# design.net
KiCad netlist of a schematic drawn in Altium Designer
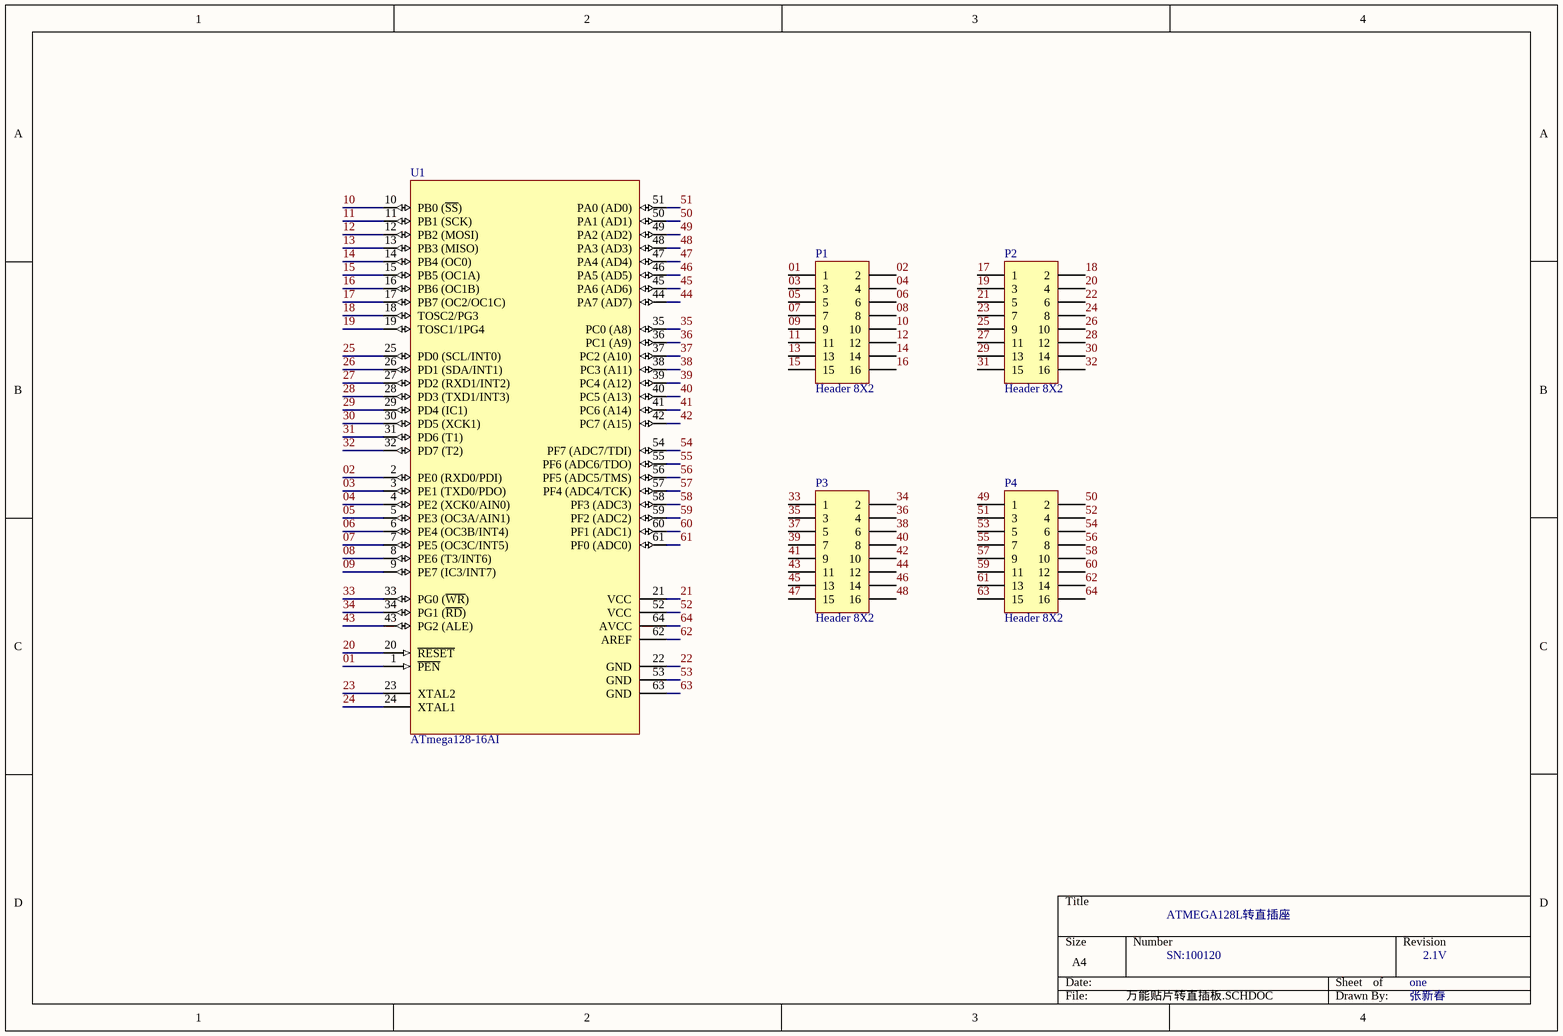
[diagram p0: 万能贴片转直插板.SCHDOC]

(export (version "E")
  (design (tool "Eeschema 10.0.6"))
  (components
    (comp (ref "P1")
      (value "Header 8X2")
      (footprint "HDR2X8")
      (description "Header, 8-Pin, Dual row")
      (fields (field (name "PUBLISHER") "Altium Limited"))
      (libsource (lib "Miscellaneous Connectors") (part "Header 8X2"))
    )
    (comp (ref "P2")
      (value "Header 8X2")
      (footprint "HDR2X8")
      (description "Header, 8-Pin, Dual row")
      (fields (field (name "PUBLISHER") "Altium Limited"))
      (libsource (lib "Miscellaneous Connectors") (part "Header 8X2"))
    )
    (comp (ref "P3")
      (value "Header 8X2")
      (footprint "HDR2X8")
      (description "Header, 8-Pin, Dual row")
      (fields (field (name "PUBLISHER") "Altium Limited"))
      (libsource (lib "Miscellaneous Connectors") (part "Header 8X2"))
    )
    (comp (ref "P4")
      (value "Header 8X2")
      (footprint "HDR2X8")
      (description "Header, 8-Pin, Dual row")
      (fields (field (name "PUBLISHER") "Altium Limited"))
      (libsource (lib "Miscellaneous Connectors") (part "Header 8X2"))
    )
    (comp (ref "U1")
      (value "ATmega128-16AI")
      (footprint "wanneng_2")
      (description "8-Bit AVR Microcontroller with 128K Bytes of In-System Programmable Flash Memory")
      (fields (field (name "PUBLISHER") "Altium Limited"))
      (libsource (lib "Atmel Microcontroller 8-Bit AVR") (part "ATmega128-16AI"))
    )
  )
  (nets
    (net (code "1") (name "/01") (class "Default")
      (node (ref "P1") (pin "1") (pinfunction "1_1") (pintype "passive"))
      (node (ref "U1") (pin "1") (pinfunction "~{PEN}_1") (pintype "input"))
    )
    (net (code "2") (name "/02") (class "Default")
      (node (ref "P1") (pin "2") (pinfunction "2_2") (pintype "passive"))
      (node (ref "U1") (pin "2") (pinfunction "PE0_(RXD0/PDI)_2") (pintype "bidirectional"))
    )
    (net (code "3") (name "/03") (class "Default")
      (node (ref "P1") (pin "3") (pinfunction "3_3") (pintype "passive"))
      (node (ref "U1") (pin "3") (pinfunction "PE1_(TXD0/PDO)_3") (pintype "bidirectional"))
    )
    (net (code "4") (name "/04") (class "Default")
      (node (ref "P1") (pin "4") (pinfunction "4_4") (pintype "passive"))
      (node (ref "U1") (pin "4") (pinfunction "PE2_(XCK0/AIN0)_4") (pintype "bidirectional"))
    )
    (net (code "5") (name "/05") (class "Default")
      (node (ref "P1") (pin "5") (pinfunction "5_5") (pintype "passive"))
      (node (ref "U1") (pin "5") (pinfunction "PE3_(OC3A/AIN1)_5") (pintype "bidirectional"))
    )
    (net (code "6") (name "/06") (class "Default")
      (node (ref "P1") (pin "6") (pinfunction "6_6") (pintype "passive"))
      (node (ref "U1") (pin "6") (pinfunction "PE4_(OC3B/INT4)_6") (pintype "bidirectional"))
    )
    (net (code "7") (name "/07") (class "Default")
      (node (ref "P1") (pin "7") (pinfunction "7_7") (pintype "passive"))
      (node (ref "U1") (pin "7") (pinfunction "PE5_(OC3C/INT5)_7") (pintype "bidirectional"))
    )
    (net (code "8") (name "/08") (class "Default")
      (node (ref "P1") (pin "8") (pinfunction "8_8") (pintype "passive"))
      (node (ref "U1") (pin "8") (pinfunction "PE6_(T3/INT6)_8") (pintype "bidirectional"))
    )
    (net (code "9") (name "/09") (class "Default")
      (node (ref "P1") (pin "9") (pinfunction "9_9") (pintype "passive"))
      (node (ref "U1") (pin "9") (pinfunction "PE7_(IC3/INT7)_9") (pintype "bidirectional"))
    )
    (net (code "10") (name "/10") (class "Default")
      (node (ref "P1") (pin "10") (pinfunction "10_10") (pintype "passive"))
      (node (ref "U1") (pin "10") (pinfunction "PB0_(~{SS})_10") (pintype "bidirectional"))
    )
    (net (code "11") (name "/11") (class "Default")
      (node (ref "P1") (pin "11") (pinfunction "11_11") (pintype "passive"))
      (node (ref "U1") (pin "11") (pinfunction "PB1_(SCK)_11") (pintype "bidirectional"))
    )
    (net (code "12") (name "/12") (class "Default")
      (node (ref "P1") (pin "12") (pinfunction "12_12") (pintype "passive"))
      (node (ref "U1") (pin "12") (pinfunction "PB2_(MOSI)_12") (pintype "bidirectional"))
    )
    (net (code "13") (name "/13") (class "Default")
      (node (ref "P1") (pin "13") (pinfunction "13_13") (pintype "passive"))
      (node (ref "U1") (pin "13") (pinfunction "PB3_(MISO)_13") (pintype "bidirectional"))
    )
    (net (code "14") (name "/14") (class "Default")
      (node (ref "P1") (pin "14") (pinfunction "14_14") (pintype "passive"))
      (node (ref "U1") (pin "14") (pinfunction "PB4_(OC0)_14") (pintype "bidirectional"))
    )
    (net (code "15") (name "/15") (class "Default")
      (node (ref "P1") (pin "15") (pinfunction "15_15") (pintype "passive"))
      (node (ref "U1") (pin "15") (pinfunction "PB5_(OC1A)_15") (pintype "bidirectional"))
    )
    (net (code "16") (name "/16") (class "Default")
      (node (ref "P1") (pin "16") (pinfunction "16_16") (pintype "passive"))
      (node (ref "U1") (pin "16") (pinfunction "PB6_(OC1B)_16") (pintype "bidirectional"))
    )
    (net (code "17") (name "/17") (class "Default")
      (node (ref "P2") (pin "1") (pinfunction "1_1") (pintype "passive"))
      (node (ref "U1") (pin "17") (pinfunction "PB7_(OC2/OC1C)_17") (pintype "bidirectional"))
    )
    (net (code "18") (name "/18") (class "Default")
      (node (ref "P2") (pin "2") (pinfunction "2_2") (pintype "passive"))
      (node (ref "U1") (pin "18") (pinfunction "TOSC2/PG3_18") (pintype "bidirectional"))
    )
    (net (code "19") (name "/19") (class "Default")
      (node (ref "P2") (pin "3") (pinfunction "3_3") (pintype "passive"))
      (node (ref "U1") (pin "19") (pinfunction "TOSC1/1PG4_19") (pintype "bidirectional"))
    )
    (net (code "20") (name "/20") (class "Default")
      (node (ref "P2") (pin "4") (pinfunction "4_4") (pintype "passive"))
      (node (ref "U1") (pin "20") (pinfunction "~{RESET}_20") (pintype "input"))
    )
    (net (code "21") (name "/21") (class "Default")
      (node (ref "P2") (pin "5") (pinfunction "5_5") (pintype "passive"))
      (node (ref "U1") (pin "21") (pinfunction "VCC_21") (pintype "power_in"))
    )
    (net (code "22") (name "/22") (class "Default")
      (node (ref "P2") (pin "6") (pinfunction "6_6") (pintype "passive"))
      (node (ref "U1") (pin "22") (pinfunction "GND_22") (pintype "power_in"))
    )
    (net (code "23") (name "/23") (class "Default")
      (node (ref "P2") (pin "7") (pinfunction "7_7") (pintype "passive"))
      (node (ref "U1") (pin "23") (pinfunction "XTAL2_23") (pintype "passive"))
    )
    (net (code "24") (name "/24") (class "Default")
      (node (ref "P2") (pin "8") (pinfunction "8_8") (pintype "passive"))
      (node (ref "U1") (pin "24") (pinfunction "XTAL1_24") (pintype "passive"))
    )
    (net (code "25") (name "/25") (class "Default")
      (node (ref "P2") (pin "9") (pinfunction "9_9") (pintype "passive"))
      (node (ref "U1") (pin "25") (pinfunction "PD0_(SCL/INT0)_25") (pintype "bidirectional"))
    )
    (net (code "26") (name "/26") (class "Default")
      (node (ref "P2") (pin "10") (pinfunction "10_10") (pintype "passive"))
      (node (ref "U1") (pin "26") (pinfunction "PD1_(SDA/INT1)_26") (pintype "bidirectional"))
    )
    (net (code "27") (name "/27") (class "Default")
      (node (ref "P2") (pin "11") (pinfunction "11_11") (pintype "passive"))
      (node (ref "U1") (pin "27") (pinfunction "PD2_(RXD1/INT2)_27") (pintype "bidirectional"))
    )
    (net (code "28") (name "/28") (class "Default")
      (node (ref "P2") (pin "12") (pinfunction "12_12") (pintype "passive"))
      (node (ref "U1") (pin "28") (pinfunction "PD3_(TXD1/INT3)_28") (pintype "bidirectional"))
    )
    (net (code "29") (name "/29") (class "Default")
      (node (ref "P2") (pin "13") (pinfunction "13_13") (pintype "passive"))
      (node (ref "U1") (pin "29") (pinfunction "PD4_(IC1)_29") (pintype "bidirectional"))
    )
    (net (code "30") (name "/30") (class "Default")
      (node (ref "P2") (pin "14") (pinfunction "14_14") (pintype "passive"))
      (node (ref "U1") (pin "30") (pinfunction "PD5_(XCK1)_30") (pintype "bidirectional"))
    )
    (net (code "31") (name "/31") (class "Default")
      (node (ref "P2") (pin "15") (pinfunction "15_15") (pintype "passive"))
      (node (ref "U1") (pin "31") (pinfunction "PD6_(T1)_31") (pintype "bidirectional"))
    )
    (net (code "32") (name "/32") (class "Default")
      (node (ref "P2") (pin "16") (pinfunction "16_16") (pintype "passive"))
      (node (ref "U1") (pin "32") (pinfunction "PD7_(T2)_32") (pintype "bidirectional"))
    )
    (net (code "33") (name "/33") (class "Default")
      (node (ref "P3") (pin "1") (pinfunction "1_1") (pintype "passive"))
      (node (ref "U1") (pin "33") (pinfunction "PG0_(~{WR})_33") (pintype "bidirectional"))
    )
    (net (code "34") (name "/34") (class "Default")
      (node (ref "P3") (pin "2") (pinfunction "2_2") (pintype "passive"))
      (node (ref "U1") (pin "34") (pinfunction "PG1_(~{RD})_34") (pintype "bidirectional"))
    )
    (net (code "35") (name "/35") (class "Default")
      (node (ref "P3") (pin "3") (pinfunction "3_3") (pintype "passive"))
      (node (ref "U1") (pin "35") (pinfunction "PC0_(A8)_35") (pintype "bidirectional"))
    )
    (net (code "36") (name "/36") (class "Default")
      (node (ref "P3") (pin "4") (pinfunction "4_4") (pintype "passive"))
      (node (ref "U1") (pin "36") (pinfunction "PC1_(A9)_36") (pintype "bidirectional"))
    )
    (net (code "37") (name "/37") (class "Default")
      (node (ref "P3") (pin "5") (pinfunction "5_5") (pintype "passive"))
      (node (ref "U1") (pin "37") (pinfunction "PC2_(A10)_37") (pintype "bidirectional"))
    )
    (net (code "38") (name "/38") (class "Default")
      (node (ref "P3") (pin "6") (pinfunction "6_6") (pintype "passive"))
      (node (ref "U1") (pin "38") (pinfunction "PC3_(A11)_38") (pintype "bidirectional"))
    )
    (net (code "39") (name "/39") (class "Default")
      (node (ref "P3") (pin "7") (pinfunction "7_7") (pintype "passive"))
      (node (ref "U1") (pin "39") (pinfunction "PC4_(A12)_39") (pintype "bidirectional"))
    )
    (net (code "40") (name "/40") (class "Default")
      (node (ref "P3") (pin "8") (pinfunction "8_8") (pintype "passive"))
      (node (ref "U1") (pin "40") (pinfunction "PC5_(A13)_40") (pintype "bidirectional"))
    )
    (net (code "41") (name "/41") (class "Default")
      (node (ref "P3") (pin "9") (pinfunction "9_9") (pintype "passive"))
      (node (ref "U1") (pin "41") (pinfunction "PC6_(A14)_41") (pintype "bidirectional"))
    )
    (net (code "42") (name "/42") (class "Default")
      (node (ref "P3") (pin "10") (pinfunction "10_10") (pintype "passive"))
      (node (ref "U1") (pin "42") (pinfunction "PC7_(A15)_42") (pintype "bidirectional"))
    )
    (net (code "43") (name "/43") (class "Default")
      (node (ref "P3") (pin "11") (pinfunction "11_11") (pintype "passive"))
      (node (ref "U1") (pin "43") (pinfunction "PG2_(ALE)_43") (pintype "bidirectional"))
    )
    (net (code "44") (name "/44") (class "Default")
      (node (ref "P3") (pin "12") (pinfunction "12_12") (pintype "passive"))
      (node (ref "U1") (pin "44") (pinfunction "PA7_(AD7)_44") (pintype "bidirectional"))
    )
    (net (code "45") (name "/45") (class "Default")
      (node (ref "P3") (pin "13") (pinfunction "13_13") (pintype "passive"))
      (node (ref "U1") (pin "45") (pinfunction "PA6_(AD6)_45") (pintype "bidirectional"))
    )
    (net (code "46") (name "/46") (class "Default")
      (node (ref "P3") (pin "14") (pinfunction "14_14") (pintype "passive"))
      (node (ref "U1") (pin "46") (pinfunction "PA5_(AD5)_46") (pintype "bidirectional"))
    )
    (net (code "47") (name "/47") (class "Default")
      (node (ref "P3") (pin "15") (pinfunction "15_15") (pintype "passive"))
      (node (ref "U1") (pin "47") (pinfunction "PA4_(AD4)_47") (pintype "bidirectional"))
    )
    (net (code "48") (name "/48") (class "Default")
      (node (ref "P3") (pin "16") (pinfunction "16_16") (pintype "passive"))
      (node (ref "U1") (pin "48") (pinfunction "PA3_(AD3)_48") (pintype "bidirectional"))
    )
    (net (code "49") (name "/49") (class "Default")
      (node (ref "P4") (pin "1") (pinfunction "1_1") (pintype "passive"))
      (node (ref "U1") (pin "49") (pinfunction "PA2_(AD2)_49") (pintype "bidirectional"))
    )
    (net (code "50") (name "/50") (class "Default")
      (node (ref "P4") (pin "2") (pinfunction "2_2") (pintype "passive"))
      (node (ref "U1") (pin "50") (pinfunction "PA1_(AD1)_50") (pintype "bidirectional"))
    )
    (net (code "51") (name "/51") (class "Default")
      (node (ref "P4") (pin "3") (pinfunction "3_3") (pintype "passive"))
      (node (ref "U1") (pin "51") (pinfunction "PA0_(AD0)_51") (pintype "bidirectional"))
    )
    (net (code "52") (name "/52") (class "Default")
      (node (ref "P4") (pin "4") (pinfunction "4_4") (pintype "passive"))
      (node (ref "U1") (pin "52") (pinfunction "VCC_52") (pintype "power_in"))
    )
    (net (code "53") (name "/53") (class "Default")
      (node (ref "P4") (pin "5") (pinfunction "5_5") (pintype "passive"))
      (node (ref "U1") (pin "53") (pinfunction "GND_53") (pintype "power_in"))
    )
    (net (code "54") (name "/54") (class "Default")
      (node (ref "P4") (pin "6") (pinfunction "6_6") (pintype "passive"))
      (node (ref "U1") (pin "54") (pinfunction "PF7_(ADC7/TDI)_54") (pintype "bidirectional"))
    )
    (net (code "55") (name "/55") (class "Default")
      (node (ref "P4") (pin "7") (pinfunction "7_7") (pintype "passive"))
      (node (ref "U1") (pin "55") (pinfunction "PF6_(ADC6/TDO)_55") (pintype "bidirectional"))
    )
    (net (code "56") (name "/56") (class "Default")
      (node (ref "P4") (pin "8") (pinfunction "8_8") (pintype "passive"))
      (node (ref "U1") (pin "56") (pinfunction "PF5_(ADC5/TMS)_56") (pintype "bidirectional"))
    )
    (net (code "57") (name "/57") (class "Default")
      (node (ref "P4") (pin "9") (pinfunction "9_9") (pintype "passive"))
      (node (ref "U1") (pin "57") (pinfunction "PF4_(ADC4/TCK)_57") (pintype "bidirectional"))
    )
    (net (code "58") (name "/58") (class "Default")
      (node (ref "P4") (pin "10") (pinfunction "10_10") (pintype "passive"))
      (node (ref "U1") (pin "58") (pinfunction "PF3_(ADC3)_58") (pintype "bidirectional"))
    )
    (net (code "59") (name "/59") (class "Default")
      (node (ref "P4") (pin "11") (pinfunction "11_11") (pintype "passive"))
      (node (ref "U1") (pin "59") (pinfunction "PF2_(ADC2)_59") (pintype "bidirectional"))
    )
    (net (code "60") (name "/60") (class "Default")
      (node (ref "P4") (pin "12") (pinfunction "12_12") (pintype "passive"))
      (node (ref "U1") (pin "60") (pinfunction "PF1_(ADC1)_60") (pintype "bidirectional"))
    )
    (net (code "61") (name "/61") (class "Default")
      (node (ref "P4") (pin "13") (pinfunction "13_13") (pintype "passive"))
      (node (ref "U1") (pin "61") (pinfunction "PF0_(ADC0)_61") (pintype "bidirectional"))
    )
    (net (code "62") (name "/62") (class "Default")
      (node (ref "P4") (pin "14") (pinfunction "14_14") (pintype "passive"))
      (node (ref "U1") (pin "62") (pinfunction "AREF_62") (pintype "passive"))
    )
    (net (code "63") (name "/63") (class "Default")
      (node (ref "P4") (pin "15") (pinfunction "15_15") (pintype "passive"))
      (node (ref "U1") (pin "63") (pinfunction "GND_63") (pintype "power_in"))
    )
    (net (code "64") (name "/64") (class "Default")
      (node (ref "P4") (pin "16") (pinfunction "16_16") (pintype "passive"))
      (node (ref "U1") (pin "64") (pinfunction "AVCC_64") (pintype "power_in"))
    )
  )
)
